# dac.net
KiCad netlist of a schematic drawn in EAGLE
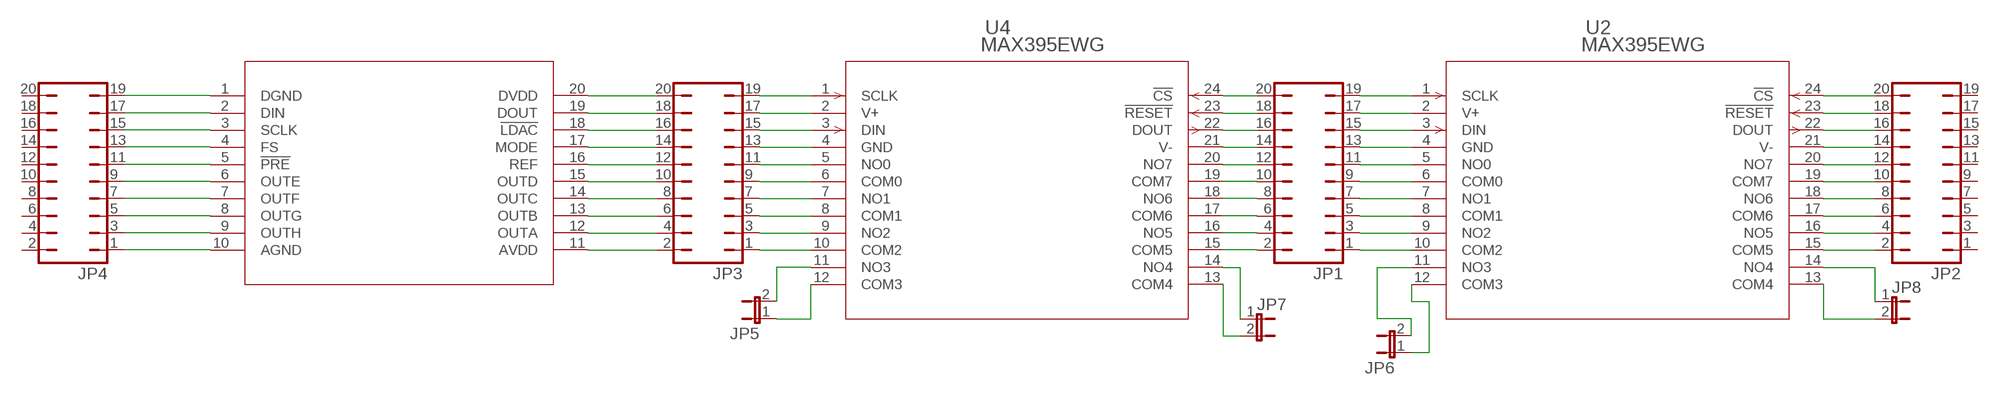
[diagram p0: schematic, sheet 1]

(export (version "E")
  (design (tool "Eeschema 10.0.6"))
  (components
    (comp (ref "JP1")
      (value "JP10Q")
      (footprint "eagle-import:JP10Q")
      (libsource (lib "eagle-import") (part "JP10Q"))
    )
    (comp (ref "JP2")
      (value "JP10Q")
      (footprint "eagle-import:JP10Q")
      (libsource (lib "eagle-import") (part "JP10Q"))
    )
    (comp (ref "JP3")
      (value "JP10Q")
      (footprint "eagle-import:JP10Q")
      (libsource (lib "eagle-import") (part "JP10Q"))
    )
    (comp (ref "JP4")
      (value "JP10Q")
      (footprint "eagle-import:JP10Q")
      (libsource (lib "eagle-import") (part "JP10Q"))
    )
    (comp (ref "JP5")
      (value "JP1E")
      (footprint "eagle-import:JP1")
      (libsource (lib "eagle-import") (part "JP1E"))
    )
    (comp (ref "JP6")
      (value "JP1E")
      (footprint "eagle-import:JP1")
      (libsource (lib "eagle-import") (part "JP1E"))
    )
    (comp (ref "JP7")
      (value "JP1E")
      (footprint "eagle-import:JP1")
      (libsource (lib "eagle-import") (part "JP1E"))
    )
    (comp (ref "JP8")
      (value "JP1E")
      (footprint "eagle-import:JP1")
      (libsource (lib "eagle-import") (part "JP1E"))
    )
    (comp (ref "U1")
      (value "TLV5610_DW_20")
      (footprint "eagle-import:DW20")
      (libsource (lib "eagle-import") (part "TLV5610_DW_20"))
    )
    (comp (ref "U2")
      (value "MAX395EWG")
      (footprint "eagle-import:21-0042B_24")
      (fields (field (name "MANUFACTURER_PART_NUMBER") "max395ewg"))
      (libsource (lib "eagle-import") (part "MAX395EWG"))
    )
    (comp (ref "U4")
      (value "MAX395EWG")
      (footprint "eagle-import:21-0042B_24")
      (fields (field (name "MANUFACTURER_PART_NUMBER") "max395ewg"))
      (libsource (lib "eagle-import") (part "MAX395EWG"))
    )
  )
  (nets
    (net (code "1") (name "Net-(U1-AGND)") (class "Default")
      (node (ref "JP4") (pin "1") (pinfunction "1_1") (pintype "passive"))
      (node (ref "U1") (pin "10") (pinfunction "AGND_10") (pintype "power_in"))
    )
    (net (code "2") (name "Net-(U1-AVDD)") (class "Default")
      (node (ref "JP3") (pin "2") (pinfunction "2_2") (pintype "passive"))
      (node (ref "U1") (pin "11") (pinfunction "AVDD_11") (pintype "power_in"))
    )
    (net (code "3") (name "Net-(U1-DGND)") (class "Default")
      (node (ref "JP4") (pin "19") (pinfunction "19_19") (pintype "passive"))
      (node (ref "U1") (pin "1") (pinfunction "DGND_1") (pintype "power_in"))
    )
    (net (code "4") (name "Net-(U1-DIN)") (class "Default")
      (node (ref "JP4") (pin "17") (pinfunction "17_17") (pintype "passive"))
      (node (ref "U1") (pin "2") (pinfunction "DIN_2") (pintype "input"))
    )
    (net (code "5") (name "Net-(U1-DOUT)") (class "Default")
      (node (ref "JP3") (pin "18") (pinfunction "18_18") (pintype "passive"))
      (node (ref "U1") (pin "19") (pinfunction "DOUT_19") (pintype "output"))
    )
    (net (code "6") (name "Net-(U1-DVDD)") (class "Default")
      (node (ref "JP3") (pin "20") (pinfunction "20_20") (pintype "passive"))
      (node (ref "U1") (pin "20") (pinfunction "DVDD_20") (pintype "power_in"))
    )
    (net (code "7") (name "Net-(U1-FS)") (class "Default")
      (node (ref "JP4") (pin "13") (pinfunction "13_13") (pintype "passive"))
      (node (ref "U1") (pin "4") (pinfunction "FS_4") (pintype "input"))
    )
    (net (code "8") (name "Net-(U1-MODE)") (class "Default")
      (node (ref "JP3") (pin "14") (pinfunction "14_14") (pintype "passive"))
      (node (ref "U1") (pin "17") (pinfunction "MODE_17") (pintype "input"))
    )
    (net (code "9") (name "Net-(U1-OUTA)") (class "Default")
      (node (ref "JP3") (pin "4") (pinfunction "4_4") (pintype "passive"))
      (node (ref "U1") (pin "12") (pinfunction "OUTA_12") (pintype "output"))
    )
    (net (code "10") (name "Net-(U1-OUTB)") (class "Default")
      (node (ref "JP3") (pin "6") (pinfunction "6_6") (pintype "passive"))
      (node (ref "U1") (pin "13") (pinfunction "OUTB_13") (pintype "output"))
    )
    (net (code "11") (name "Net-(U1-OUTC)") (class "Default")
      (node (ref "JP3") (pin "8") (pinfunction "8_8") (pintype "passive"))
      (node (ref "U1") (pin "14") (pinfunction "OUTC_14") (pintype "output"))
    )
    (net (code "12") (name "Net-(U1-OUTD)") (class "Default")
      (node (ref "JP3") (pin "10") (pinfunction "10_10") (pintype "passive"))
      (node (ref "U1") (pin "15") (pinfunction "OUTD_15") (pintype "output"))
    )
    (net (code "13") (name "Net-(U1-OUTE)") (class "Default")
      (node (ref "JP4") (pin "9") (pinfunction "9_9") (pintype "passive"))
      (node (ref "U1") (pin "6") (pinfunction "OUTE_6") (pintype "output"))
    )
    (net (code "14") (name "Net-(U1-OUTF)") (class "Default")
      (node (ref "JP4") (pin "7") (pinfunction "7_7") (pintype "passive"))
      (node (ref "U1") (pin "7") (pinfunction "OUTF_7") (pintype "output"))
    )
    (net (code "15") (name "Net-(U1-OUTG)") (class "Default")
      (node (ref "JP4") (pin "5") (pinfunction "5_5") (pintype "passive"))
      (node (ref "U1") (pin "8") (pinfunction "OUTG_8") (pintype "output"))
    )
    (net (code "16") (name "Net-(U1-OUTH)") (class "Default")
      (node (ref "JP4") (pin "3") (pinfunction "3_3") (pintype "passive"))
      (node (ref "U1") (pin "9") (pinfunction "OUTH_9") (pintype "output"))
    )
    (net (code "17") (name "Net-(U1-REF)") (class "Default")
      (node (ref "JP3") (pin "12") (pinfunction "12_12") (pintype "passive"))
      (node (ref "U1") (pin "16") (pinfunction "REF_16") (pintype "input"))
    )
    (net (code "18") (name "Net-(U1-SCLK)") (class "Default")
      (node (ref "JP4") (pin "15") (pinfunction "15_15") (pintype "passive"))
      (node (ref "U1") (pin "3") (pinfunction "SCLK_3") (pintype "input"))
    )
    (net (code "19") (name "Net-(U1-~{LDAC})") (class "Default")
      (node (ref "JP3") (pin "16") (pinfunction "16_16") (pintype "passive"))
      (node (ref "U1") (pin "18") (pinfunction "~{LDAC}_18") (pintype "input"))
    )
    (net (code "20") (name "Net-(U1-~{PRE})") (class "Default")
      (node (ref "JP4") (pin "11") (pinfunction "11_11") (pintype "passive"))
      (node (ref "U1") (pin "5") (pinfunction "~{PRE}_5") (pintype "input"))
    )
    (net (code "21") (name "Net-(U2-COM0)") (class "Default")
      (node (ref "JP1") (pin "9") (pinfunction "9_9") (pintype "passive"))
      (node (ref "U2") (pin "6") (pinfunction "COM0_6") (pintype "passive"))
    )
    (net (code "22") (name "Net-(U2-COM1)") (class "Default")
      (node (ref "JP1") (pin "5") (pinfunction "5_5") (pintype "passive"))
      (node (ref "U2") (pin "8") (pinfunction "COM1_8") (pintype "passive"))
    )
    (net (code "23") (name "Net-(U2-COM2)") (class "Default")
      (node (ref "JP1") (pin "1") (pinfunction "1_1") (pintype "passive"))
      (node (ref "U2") (pin "10") (pinfunction "COM2_10") (pintype "passive"))
    )
    (net (code "24") (name "Net-(U2-COM3)") (class "Default")
      (node (ref "JP6") (pin "1") (pinfunction "1_1") (pintype "passive"))
      (node (ref "U2") (pin "12") (pinfunction "COM3_12") (pintype "passive"))
    )
    (net (code "25") (name "Net-(U2-COM4)") (class "Default")
      (node (ref "JP8") (pin "2") (pinfunction "2_2") (pintype "passive"))
      (node (ref "U2") (pin "13") (pinfunction "COM4_13") (pintype "passive"))
    )
    (net (code "26") (name "Net-(U2-COM5)") (class "Default")
      (node (ref "JP2") (pin "2") (pinfunction "2_2") (pintype "passive"))
      (node (ref "U2") (pin "15") (pinfunction "COM5_15") (pintype "passive"))
    )
    (net (code "27") (name "Net-(U2-COM6)") (class "Default")
      (node (ref "JP2") (pin "6") (pinfunction "6_6") (pintype "passive"))
      (node (ref "U2") (pin "17") (pinfunction "COM6_17") (pintype "passive"))
    )
    (net (code "28") (name "Net-(U2-COM7)") (class "Default")
      (node (ref "JP2") (pin "10") (pinfunction "10_10") (pintype "passive"))
      (node (ref "U2") (pin "19") (pinfunction "COM7_19") (pintype "passive"))
    )
    (net (code "29") (name "Net-(U2-DIN)") (class "Default")
      (node (ref "JP1") (pin "15") (pinfunction "15_15") (pintype "passive"))
      (node (ref "U2") (pin "3") (pinfunction "DIN_3") (pintype "input"))
    )
    (net (code "30") (name "Net-(U2-DOUT)") (class "Default")
      (node (ref "JP2") (pin "16") (pinfunction "16_16") (pintype "passive"))
      (node (ref "U2") (pin "22") (pinfunction "DOUT_22") (pintype "output"))
    )
    (net (code "31") (name "Net-(U2-GND)") (class "Default")
      (node (ref "JP1") (pin "13") (pinfunction "13_13") (pintype "passive"))
      (node (ref "U2") (pin "4") (pinfunction "GND_4") (pintype "power_in"))
    )
    (net (code "32") (name "Net-(U2-NO0)") (class "Default")
      (node (ref "JP1") (pin "11") (pinfunction "11_11") (pintype "passive"))
      (node (ref "U2") (pin "5") (pinfunction "NO0_5") (pintype "passive"))
    )
    (net (code "33") (name "Net-(U2-NO1)") (class "Default")
      (node (ref "JP1") (pin "7") (pinfunction "7_7") (pintype "passive"))
      (node (ref "U2") (pin "7") (pinfunction "NO1_7") (pintype "passive"))
    )
    (net (code "34") (name "Net-(U2-NO2)") (class "Default")
      (node (ref "JP1") (pin "3") (pinfunction "3_3") (pintype "passive"))
      (node (ref "U2") (pin "9") (pinfunction "NO2_9") (pintype "passive"))
    )
    (net (code "35") (name "Net-(U2-NO3)") (class "Default")
      (node (ref "JP6") (pin "2") (pinfunction "2_2") (pintype "passive"))
      (node (ref "U2") (pin "11") (pinfunction "NO3_11") (pintype "passive"))
    )
    (net (code "36") (name "Net-(U2-NO4)") (class "Default")
      (node (ref "JP8") (pin "1") (pinfunction "1_1") (pintype "passive"))
      (node (ref "U2") (pin "14") (pinfunction "NO4_14") (pintype "passive"))
    )
    (net (code "37") (name "Net-(U2-NO5)") (class "Default")
      (node (ref "JP2") (pin "4") (pinfunction "4_4") (pintype "passive"))
      (node (ref "U2") (pin "16") (pinfunction "NO5_16") (pintype "passive"))
    )
    (net (code "38") (name "Net-(U2-NO6)") (class "Default")
      (node (ref "JP2") (pin "8") (pinfunction "8_8") (pintype "passive"))
      (node (ref "U2") (pin "18") (pinfunction "NO6_18") (pintype "passive"))
    )
    (net (code "39") (name "Net-(U2-NO7)") (class "Default")
      (node (ref "JP2") (pin "12") (pinfunction "12_12") (pintype "passive"))
      (node (ref "U2") (pin "20") (pinfunction "NO7_20") (pintype "passive"))
    )
    (net (code "40") (name "Net-(U2-SCLK)") (class "Default")
      (node (ref "JP1") (pin "19") (pinfunction "19_19") (pintype "passive"))
      (node (ref "U2") (pin "1") (pinfunction "SCLK_1") (pintype "input"))
    )
    (net (code "41") (name "Net-(U2-V+)") (class "Default")
      (node (ref "JP1") (pin "17") (pinfunction "17_17") (pintype "passive"))
      (node (ref "U2") (pin "2") (pinfunction "V+_2") (pintype "power_in"))
    )
    (net (code "42") (name "Net-(U2-V-)") (class "Default")
      (node (ref "JP2") (pin "14") (pinfunction "14_14") (pintype "passive"))
      (node (ref "U2") (pin "21") (pinfunction "V-_21") (pintype "power_in"))
    )
    (net (code "43") (name "Net-(U2-~{CS})") (class "Default")
      (node (ref "JP2") (pin "20") (pinfunction "20_20") (pintype "passive"))
      (node (ref "U2") (pin "24") (pinfunction "~{CS}_24") (pintype "input"))
    )
    (net (code "44") (name "Net-(U2-~{RESET})") (class "Default")
      (node (ref "JP2") (pin "18") (pinfunction "18_18") (pintype "passive"))
      (node (ref "U2") (pin "23") (pinfunction "~{RESET}_23") (pintype "input"))
    )
    (net (code "45") (name "Net-(U4-COM0)") (class "Default")
      (node (ref "JP3") (pin "9") (pinfunction "9_9") (pintype "passive"))
      (node (ref "U4") (pin "6") (pinfunction "COM0_6") (pintype "passive"))
    )
    (net (code "46") (name "Net-(U4-COM1)") (class "Default")
      (node (ref "JP3") (pin "5") (pinfunction "5_5") (pintype "passive"))
      (node (ref "U4") (pin "8") (pinfunction "COM1_8") (pintype "passive"))
    )
    (net (code "47") (name "Net-(U4-COM2)") (class "Default")
      (node (ref "JP3") (pin "1") (pinfunction "1_1") (pintype "passive"))
      (node (ref "U4") (pin "10") (pinfunction "COM2_10") (pintype "passive"))
    )
    (net (code "48") (name "Net-(U4-COM3)") (class "Default")
      (node (ref "JP5") (pin "1") (pinfunction "1_1") (pintype "passive"))
      (node (ref "U4") (pin "12") (pinfunction "COM3_12") (pintype "passive"))
    )
    (net (code "49") (name "Net-(U4-COM4)") (class "Default")
      (node (ref "JP7") (pin "2") (pinfunction "2_2") (pintype "passive"))
      (node (ref "U4") (pin "13") (pinfunction "COM4_13") (pintype "passive"))
    )
    (net (code "50") (name "Net-(U4-COM5)") (class "Default")
      (node (ref "JP1") (pin "2") (pinfunction "2_2") (pintype "passive"))
      (node (ref "U4") (pin "15") (pinfunction "COM5_15") (pintype "passive"))
    )
    (net (code "51") (name "Net-(U4-COM6)") (class "Default")
      (node (ref "JP1") (pin "6") (pinfunction "6_6") (pintype "passive"))
      (node (ref "U4") (pin "17") (pinfunction "COM6_17") (pintype "passive"))
    )
    (net (code "52") (name "Net-(U4-COM7)") (class "Default")
      (node (ref "JP1") (pin "10") (pinfunction "10_10") (pintype "passive"))
      (node (ref "U4") (pin "19") (pinfunction "COM7_19") (pintype "passive"))
    )
    (net (code "53") (name "Net-(U4-DIN)") (class "Default")
      (node (ref "JP3") (pin "15") (pinfunction "15_15") (pintype "passive"))
      (node (ref "U4") (pin "3") (pinfunction "DIN_3") (pintype "input"))
    )
    (net (code "54") (name "Net-(U4-DOUT)") (class "Default")
      (node (ref "JP1") (pin "16") (pinfunction "16_16") (pintype "passive"))
      (node (ref "U4") (pin "22") (pinfunction "DOUT_22") (pintype "output"))
    )
    (net (code "55") (name "Net-(U4-GND)") (class "Default")
      (node (ref "JP3") (pin "13") (pinfunction "13_13") (pintype "passive"))
      (node (ref "U4") (pin "4") (pinfunction "GND_4") (pintype "power_in"))
    )
    (net (code "56") (name "Net-(U4-NO0)") (class "Default")
      (node (ref "JP3") (pin "11") (pinfunction "11_11") (pintype "passive"))
      (node (ref "U4") (pin "5") (pinfunction "NO0_5") (pintype "passive"))
    )
    (net (code "57") (name "Net-(U4-NO1)") (class "Default")
      (node (ref "JP3") (pin "7") (pinfunction "7_7") (pintype "passive"))
      (node (ref "U4") (pin "7") (pinfunction "NO1_7") (pintype "passive"))
    )
    (net (code "58") (name "Net-(U4-NO2)") (class "Default")
      (node (ref "JP3") (pin "3") (pinfunction "3_3") (pintype "passive"))
      (node (ref "U4") (pin "9") (pinfunction "NO2_9") (pintype "passive"))
    )
    (net (code "59") (name "Net-(U4-NO3)") (class "Default")
      (node (ref "JP5") (pin "2") (pinfunction "2_2") (pintype "passive"))
      (node (ref "U4") (pin "11") (pinfunction "NO3_11") (pintype "passive"))
    )
    (net (code "60") (name "Net-(U4-NO4)") (class "Default")
      (node (ref "JP7") (pin "1") (pinfunction "1_1") (pintype "passive"))
      (node (ref "U4") (pin "14") (pinfunction "NO4_14") (pintype "passive"))
    )
    (net (code "61") (name "Net-(U4-NO5)") (class "Default")
      (node (ref "JP1") (pin "4") (pinfunction "4_4") (pintype "passive"))
      (node (ref "U4") (pin "16") (pinfunction "NO5_16") (pintype "passive"))
    )
    (net (code "62") (name "Net-(U4-NO6)") (class "Default")
      (node (ref "JP1") (pin "8") (pinfunction "8_8") (pintype "passive"))
      (node (ref "U4") (pin "18") (pinfunction "NO6_18") (pintype "passive"))
    )
    (net (code "63") (name "Net-(U4-NO7)") (class "Default")
      (node (ref "JP1") (pin "12") (pinfunction "12_12") (pintype "passive"))
      (node (ref "U4") (pin "20") (pinfunction "NO7_20") (pintype "passive"))
    )
    (net (code "64") (name "Net-(U4-SCLK)") (class "Default")
      (node (ref "JP3") (pin "19") (pinfunction "19_19") (pintype "passive"))
      (node (ref "U4") (pin "1") (pinfunction "SCLK_1") (pintype "input"))
    )
    (net (code "65") (name "Net-(U4-V+)") (class "Default")
      (node (ref "JP3") (pin "17") (pinfunction "17_17") (pintype "passive"))
      (node (ref "U4") (pin "2") (pinfunction "V+_2") (pintype "power_in"))
    )
    (net (code "66") (name "Net-(U4-V-)") (class "Default")
      (node (ref "JP1") (pin "14") (pinfunction "14_14") (pintype "passive"))
      (node (ref "U4") (pin "21") (pinfunction "V-_21") (pintype "power_in"))
    )
    (net (code "67") (name "Net-(U4-~{CS})") (class "Default")
      (node (ref "JP1") (pin "20") (pinfunction "20_20") (pintype "passive"))
      (node (ref "U4") (pin "24") (pinfunction "~{CS}_24") (pintype "input"))
    )
    (net (code "68") (name "Net-(U4-~{RESET})") (class "Default")
      (node (ref "JP1") (pin "18") (pinfunction "18_18") (pintype "passive"))
      (node (ref "U4") (pin "23") (pinfunction "~{RESET}_23") (pintype "input"))
    )
    (net (code "69") (name "unconnected-(JP2-Pad1)") (class "Default")
      (node (ref "JP2") (pin "1") (pinfunction "1_1") (pintype "passive"))
    )
    (net (code "70") (name "unconnected-(JP2-Pad3)") (class "Default")
      (node (ref "JP2") (pin "3") (pinfunction "3_3") (pintype "passive"))
    )
    (net (code "71") (name "unconnected-(JP2-Pad5)") (class "Default")
      (node (ref "JP2") (pin "5") (pinfunction "5_5") (pintype "passive"))
    )
    (net (code "72") (name "unconnected-(JP2-Pad7)") (class "Default")
      (node (ref "JP2") (pin "7") (pinfunction "7_7") (pintype "passive"))
    )
    (net (code "73") (name "unconnected-(JP2-Pad9)") (class "Default")
      (node (ref "JP2") (pin "9") (pinfunction "9_9") (pintype "passive"))
    )
    (net (code "74") (name "unconnected-(JP2-Pad11)") (class "Default")
      (node (ref "JP2") (pin "11") (pinfunction "11_11") (pintype "passive"))
    )
    (net (code "75") (name "unconnected-(JP2-Pad13)") (class "Default")
      (node (ref "JP2") (pin "13") (pinfunction "13_13") (pintype "passive"))
    )
    (net (code "76") (name "unconnected-(JP2-Pad15)") (class "Default")
      (node (ref "JP2") (pin "15") (pinfunction "15_15") (pintype "passive"))
    )
    (net (code "77") (name "unconnected-(JP2-Pad17)") (class "Default")
      (node (ref "JP2") (pin "17") (pinfunction "17_17") (pintype "passive"))
    )
    (net (code "78") (name "unconnected-(JP2-Pad19)") (class "Default")
      (node (ref "JP2") (pin "19") (pinfunction "19_19") (pintype "passive"))
    )
    (net (code "79") (name "unconnected-(JP4-Pad2)") (class "Default")
      (node (ref "JP4") (pin "2") (pinfunction "2_2") (pintype "passive"))
    )
    (net (code "80") (name "unconnected-(JP4-Pad4)") (class "Default")
      (node (ref "JP4") (pin "4") (pinfunction "4_4") (pintype "passive"))
    )
    (net (code "81") (name "unconnected-(JP4-Pad6)") (class "Default")
      (node (ref "JP4") (pin "6") (pinfunction "6_6") (pintype "passive"))
    )
    (net (code "82") (name "unconnected-(JP4-Pad8)") (class "Default")
      (node (ref "JP4") (pin "8") (pinfunction "8_8") (pintype "passive"))
    )
    (net (code "83") (name "unconnected-(JP4-Pad10)") (class "Default")
      (node (ref "JP4") (pin "10") (pinfunction "10_10") (pintype "passive"))
    )
    (net (code "84") (name "unconnected-(JP4-Pad12)") (class "Default")
      (node (ref "JP4") (pin "12") (pinfunction "12_12") (pintype "passive"))
    )
    (net (code "85") (name "unconnected-(JP4-Pad14)") (class "Default")
      (node (ref "JP4") (pin "14") (pinfunction "14_14") (pintype "passive"))
    )
    (net (code "86") (name "unconnected-(JP4-Pad16)") (class "Default")
      (node (ref "JP4") (pin "16") (pinfunction "16_16") (pintype "passive"))
    )
    (net (code "87") (name "unconnected-(JP4-Pad18)") (class "Default")
      (node (ref "JP4") (pin "18") (pinfunction "18_18") (pintype "passive"))
    )
    (net (code "88") (name "unconnected-(JP4-Pad20)") (class "Default")
      (node (ref "JP4") (pin "20") (pinfunction "20_20") (pintype "passive"))
    )
  )
)
